# fabbot_20141102.net
KiCad netlist of a schematic drawn in EAGLE
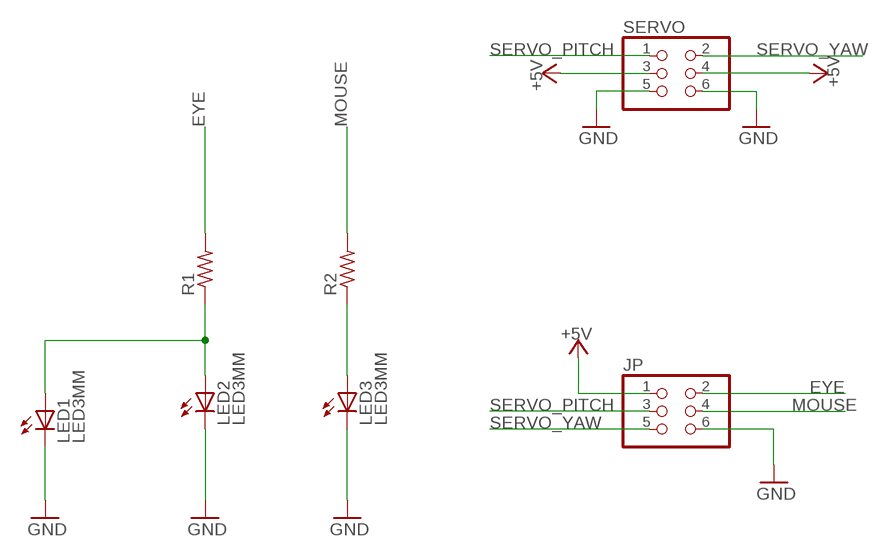
[diagram p0: schematic, sheet 1]

(export (version "E")
  (design (tool "Eeschema 10.0.6"))
  (components
    (comp (ref "JP")
      (value "PINHD-2X3/90")
      (footprint "eagle-import:2X03_90")
      (libsource (lib "eagle-import") (part "PINHD-2X3/90"))
    )
    (comp (ref "LED1")
      (value "LED3MM")
      (footprint "eagle-import:LED3MM")
      (libsource (lib "eagle-import") (part "LED3MM"))
    )
    (comp (ref "LED2")
      (value "LED3MM")
      (footprint "eagle-import:LED3MM")
      (libsource (lib "eagle-import") (part "LED3MM"))
    )
    (comp (ref "LED3")
      (value "LED3MM")
      (footprint "eagle-import:LED3MM")
      (libsource (lib "eagle-import") (part "LED3MM"))
    )
    (comp (ref "R1")
      (value "R-US_0207/10")
      (footprint "eagle-import:0207_10")
      (libsource (lib "eagle-import") (part "R-US_0207/10"))
    )
    (comp (ref "R2")
      (value "R-US_0207/10")
      (footprint "eagle-import:0207_10")
      (libsource (lib "eagle-import") (part "R-US_0207/10"))
    )
    (comp (ref "SERVO")
      (value "PINHD-2X3/90")
      (footprint "eagle-import:2X03_90")
      (libsource (lib "eagle-import") (part "PINHD-2X3/90"))
    )
  )
  (nets
    (net (code "1") (name "+5V") (class "Default")
      (node (ref "JP") (pin "1") (pinfunction "1_1") (pintype "passive"))
      (node (ref "SERVO") (pin "3") (pinfunction "3_3") (pintype "passive"))
      (node (ref "SERVO") (pin "4") (pinfunction "4_4") (pintype "passive"))
    )
    (net (code "2") (name "/EYE") (class "Default")
      (node (ref "JP") (pin "2") (pinfunction "2_2") (pintype "passive"))
      (node (ref "R1") (pin "2") (pinfunction "2_2") (pintype "passive"))
    )
    (net (code "3") (name "/MOUSE") (class "Default")
      (node (ref "JP") (pin "4") (pinfunction "4_4") (pintype "passive"))
      (node (ref "R2") (pin "2") (pinfunction "2_2") (pintype "passive"))
    )
    (net (code "4") (name "/SERVO_PITCH") (class "Default")
      (node (ref "JP") (pin "3") (pinfunction "3_3") (pintype "passive"))
      (node (ref "SERVO") (pin "1") (pinfunction "1_1") (pintype "passive"))
    )
    (net (code "5") (name "/SERVO_YAW") (class "Default")
      (node (ref "JP") (pin "5") (pinfunction "5_5") (pintype "passive"))
      (node (ref "SERVO") (pin "2") (pinfunction "2_2") (pintype "passive"))
    )
    (net (code "6") (name "GND") (class "Default")
      (node (ref "JP") (pin "6") (pinfunction "6_6") (pintype "passive"))
      (node (ref "LED1") (pin "K") (pinfunction "C_K") (pintype "passive"))
      (node (ref "LED2") (pin "K") (pinfunction "C_K") (pintype "passive"))
      (node (ref "LED3") (pin "K") (pinfunction "C_K") (pintype "passive"))
      (node (ref "SERVO") (pin "5") (pinfunction "5_5") (pintype "passive"))
      (node (ref "SERVO") (pin "6") (pinfunction "6_6") (pintype "passive"))
    )
    (net (code "7") (name "Net-(LED1-PadA)") (class "Default")
      (node (ref "LED1") (pin "A") (pinfunction "A_A") (pintype "passive"))
      (node (ref "LED2") (pin "A") (pinfunction "A_A") (pintype "passive"))
      (node (ref "R1") (pin "1") (pinfunction "1_1") (pintype "passive"))
    )
    (net (code "8") (name "Net-(LED3-PadA)") (class "Default")
      (node (ref "LED3") (pin "A") (pinfunction "A_A") (pintype "passive"))
      (node (ref "R2") (pin "1") (pinfunction "1_1") (pintype "passive"))
    )
  )
)
